# 16_-_HDMI.net
KiCad netlist of a schematic drawn in Altium Designer
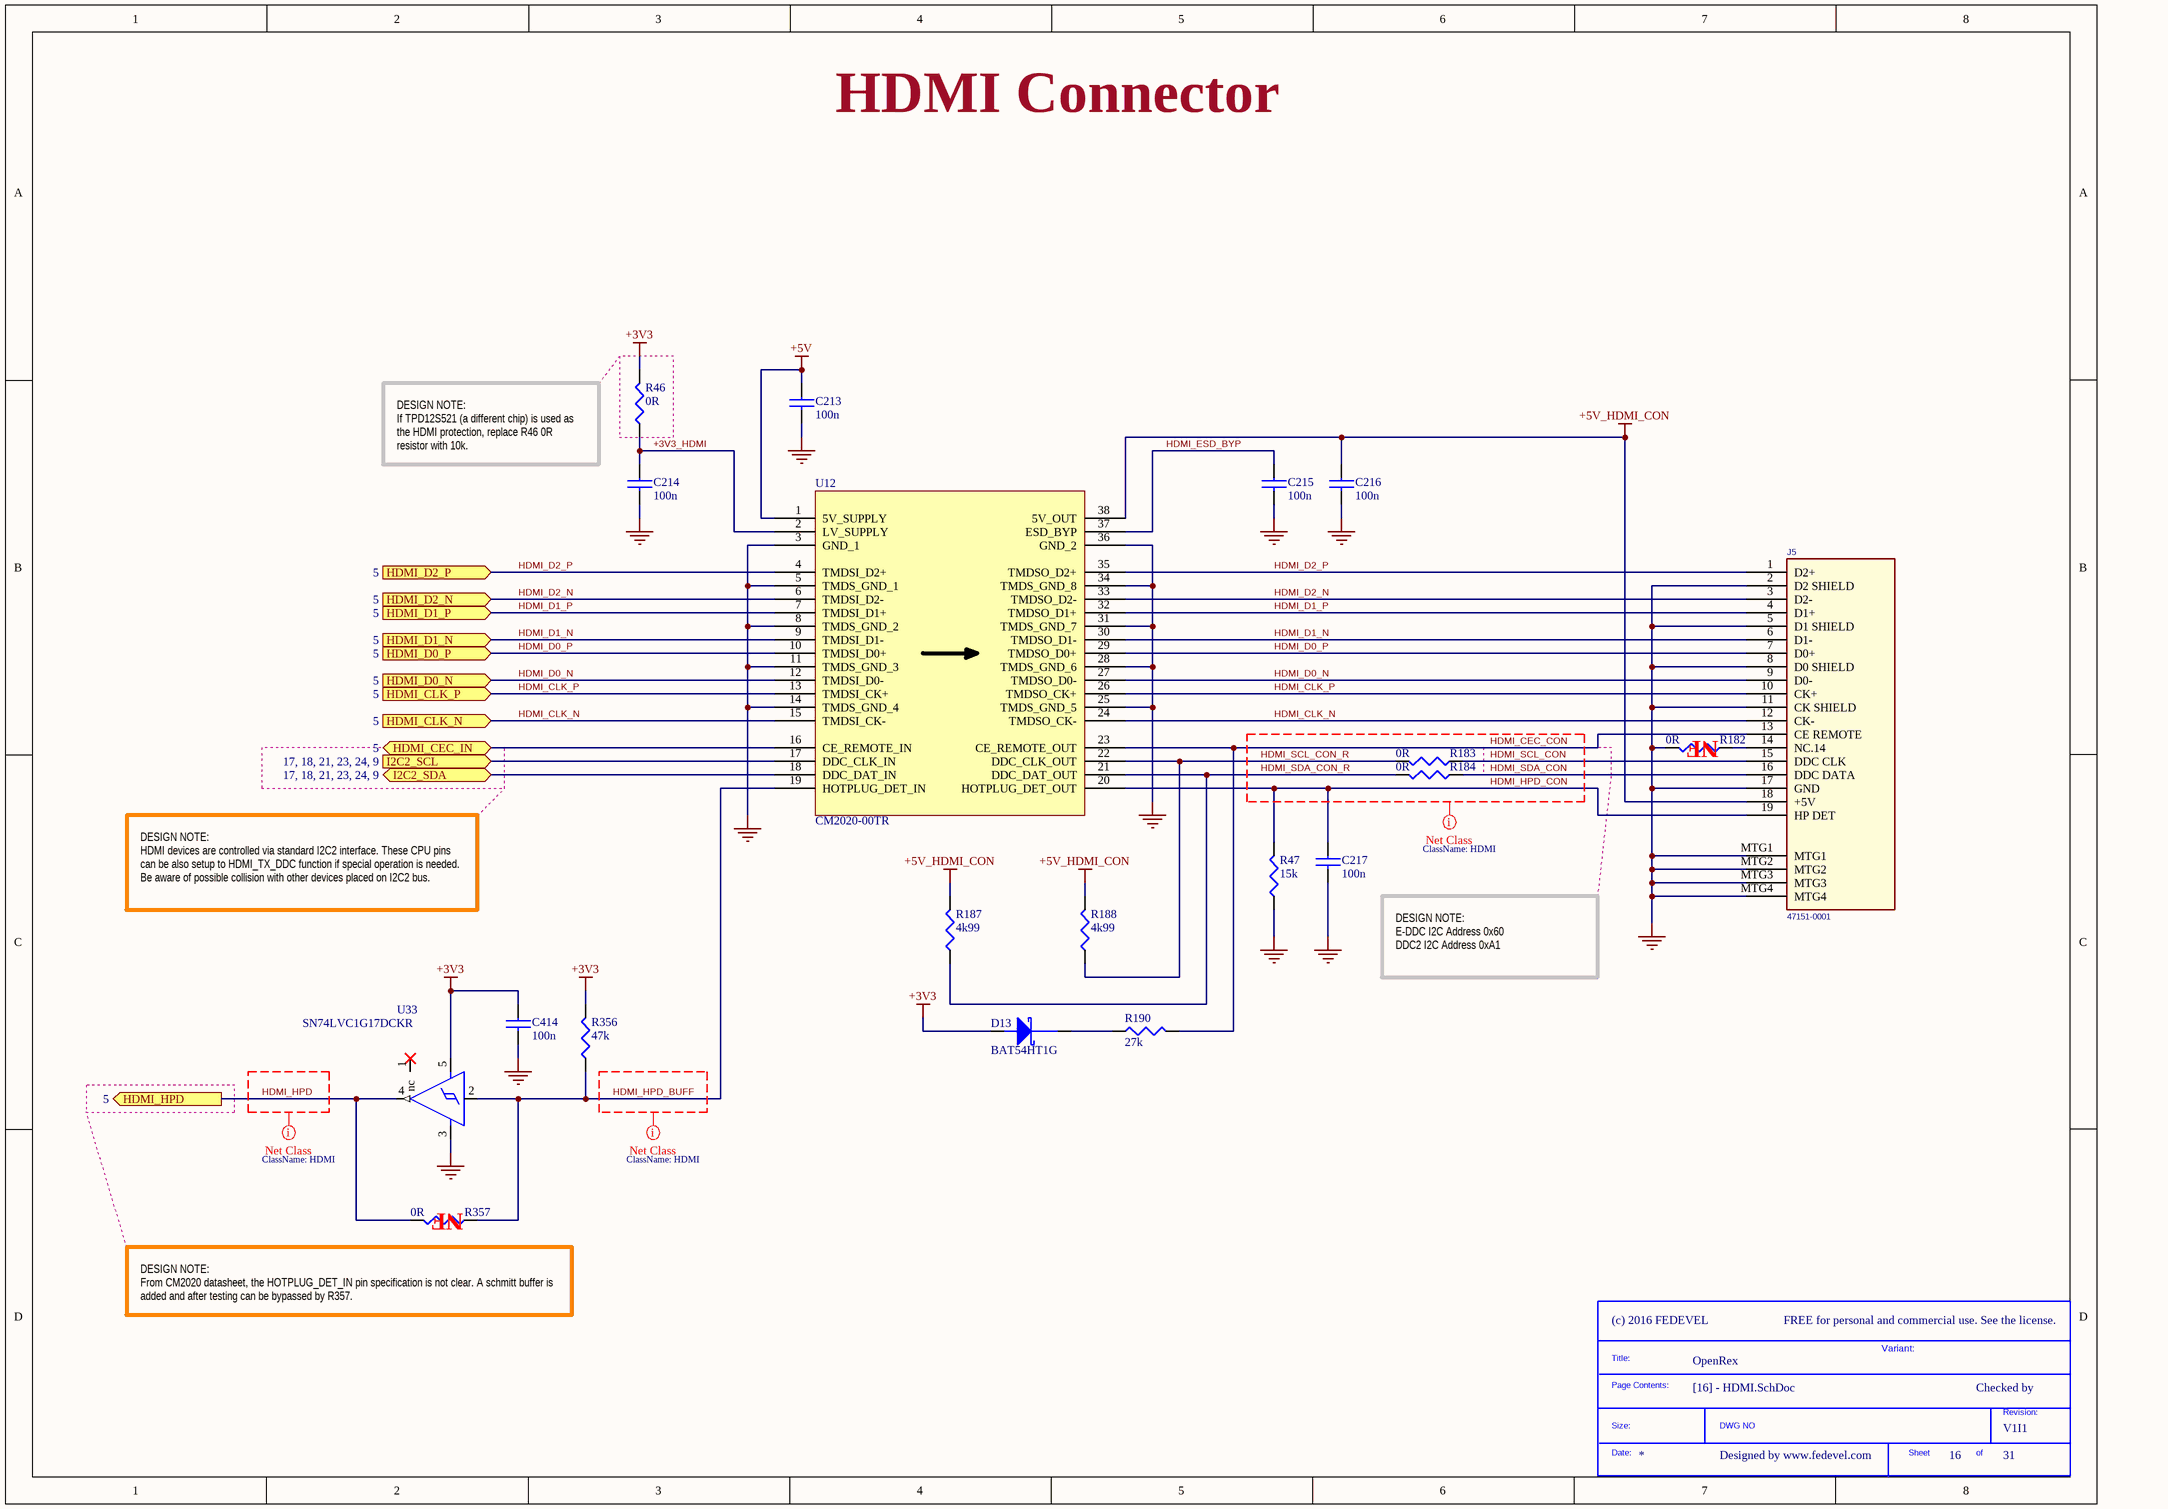
[diagram p0: [16] - HDMI.SchDoc]

(export (version "E")
  (design (tool "Eeschema 10.0.6"))
  (components
    (comp (ref "C213")
      (value "100n")
      (footprint "C0402")
      (description "CAP CER .10UF 50V X5R 10% 0402")
      (fields
        (field (name "MANUFACTURER") "TDK Corporation")
        (field (name "MANUFACTURER PART NUMBER") "C1005X5R1H104K")
      )
      (libsource (lib "Integrated_Library_FEDEVEL_APR_2015") (part "C1005X5R1H104K"))
    )
    (comp (ref "C214")
      (value "100n")
      (footprint "C0402")
      (description "CAP CER .10UF 50V X5R 10% 0402")
      (fields
        (field (name "MANUFACTURER") "TDK Corporation")
        (field (name "MANUFACTURER PART NUMBER") "C1005X5R1H104K")
      )
      (libsource (lib "Integrated_Library_FEDEVEL_APR_2015") (part "C1005X5R1H104K"))
    )
    (comp (ref "C215")
      (value "100n")
      (footprint "C0402")
      (description "CAP CER .10UF 50V X5R 10% 0402")
      (fields
        (field (name "MANUFACTURER") "TDK Corporation")
        (field (name "MANUFACTURER PART NUMBER") "C1005X5R1H104K")
      )
      (libsource (lib "Integrated_Library_FEDEVEL_APR_2015") (part "C1005X5R1H104K"))
    )
    (comp (ref "C216")
      (value "100n")
      (footprint "C0402")
      (description "CAP CER .10UF 50V X5R 10% 0402")
      (fields
        (field (name "MANUFACTURER") "TDK Corporation")
        (field (name "MANUFACTURER PART NUMBER") "C1005X5R1H104K")
      )
      (libsource (lib "Integrated_Library_FEDEVEL_APR_2015") (part "C1005X5R1H104K"))
    )
    (comp (ref "C217")
      (value "100n")
      (footprint "C0402")
      (description "CAP CER .10UF 50V X5R 10% 0402")
      (fields
        (field (name "MANUFACTURER") "TDK Corporation")
        (field (name "MANUFACTURER PART NUMBER") "C1005X5R1H104K")
      )
      (libsource (lib "Integrated_Library_FEDEVEL_APR_2015") (part "C1005X5R1H104K"))
    )
    (comp (ref "C414")
      (value "100n")
      (footprint "C0402")
      (description "CAP CER .10UF 50V X5R 10% 0402")
      (fields
        (field (name "MANUFACTURER") "TDK Corporation")
        (field (name "MANUFACTURER PART NUMBER") "C1005X5R1H104K")
      )
      (libsource (lib "Integrated_Library_FEDEVEL_APR_2015") (part "C1005X5R1H104K"))
    )
    (comp (ref "D13")
      (value "BAT54HT1G")
      (footprint "SOD323")
      (description "DIODE SCHOTTKY 30V 0.2A SOD323")
      (fields (field (name "MANUFACTURER") "Fairchild Semiconductor") (field (name ".CREATOR") "MM"))
      (libsource (lib "Integrated_Library_FEDEVEL_APR_2015") (part "BAT54HT1G"))
    )
    (comp (ref "J5")
      (value "47151-0001")
      (footprint "HDMI V1.1")
      (description "CONN RCPT 19POS HDMI RT ANG SMD")
      (fields
        (field (name "MANUFACTURER") "Molex Connector Corporation")
        (field (name ".CHECKED PCB") "MM")
        (field (name ".CHECKED SCH") "MM")
      )
      (libsource (lib "Integrated_Library_FEDEVEL_APR_2015") (part "47151-0001_v1.1"))
    )
    (comp (ref "R46")
      (value "0R")
      (footprint "R0402")
      (description "RES 0.0 OHM 1/16W 0402 SMD")
      (fields
        (field (name "MANUFACTURER") "Yageo")
        (field (name "MANUFACTURER PART NUMBER") "RC0402JR-070RL")
      )
      (libsource (lib "Integrated_Library_FEDEVEL_APR_2015") (part "RC0402JR-070RL"))
    )
    (comp (ref "R47")
      (value "15k")
      (footprint "R0402")
      (description "RES 15.0K OHM 1/16W 1% 0402 SMD")
      (fields
        (field (name "MANUFACTURER") "Yageo")
        (field (name "MANUFACTURER PART NUMBER") "RC0402FR-0715KL")
      )
      (libsource (lib "Integrated_Library_FEDEVEL_APR_2015") (part "RC0402FR-0715KL"))
    )
    (comp (ref "R182")
      (value "0R")
      (footprint "R0402")
      (description "RES 0.0 OHM 1/16W 0402 SMD")
      (fields
        (field (name "MANUFACTURER") "Yageo")
        (field (name "MANUFACTURER PART NUMBER") "RC0402JR-070RL")
      )
      (libsource (lib "Integrated_Library_FEDEVEL_APR_2015") (part "RC0402JR-070RL"))
    )
    (comp (ref "R183")
      (value "0R")
      (footprint "R0402")
      (description "RES 0.0 OHM 1/16W 0402 SMD")
      (fields
        (field (name "MANUFACTURER") "Yageo")
        (field (name "MANUFACTURER PART NUMBER") "RC0402JR-070RL")
      )
      (libsource (lib "Integrated_Library_FEDEVEL_APR_2015") (part "RC0402JR-070RL"))
    )
    (comp (ref "R184")
      (value "0R")
      (footprint "R0402")
      (description "RES 0.0 OHM 1/16W 0402 SMD")
      (fields
        (field (name "MANUFACTURER") "Yageo")
        (field (name "MANUFACTURER PART NUMBER") "RC0402JR-070RL")
      )
      (libsource (lib "Integrated_Library_FEDEVEL_APR_2015") (part "RC0402JR-070RL"))
    )
    (comp (ref "R187")
      (value "4k99")
      (footprint "R0402")
      (description "RES TF 4.99K OHM 1% 1/16W 0402")
      (fields
        (field (name "MANUFACTURER") "Stackpole Electronics Inc")
        (field (name "MANUFACTURER PART NUMBER") "RMCF0402FT4K99")
      )
      (libsource (lib "Integrated_Library_FEDEVEL_APR_2015") (part "RMCF0402FT4K99"))
    )
    (comp (ref "R188")
      (value "4k99")
      (footprint "R0402")
      (description "RES TF 4.99K OHM 1% 1/16W 0402")
      (fields
        (field (name "MANUFACTURER") "Stackpole Electronics Inc")
        (field (name "MANUFACTURER PART NUMBER") "RMCF0402FT4K99")
      )
      (libsource (lib "Integrated_Library_FEDEVEL_APR_2015") (part "RMCF0402FT4K99"))
    )
    (comp (ref "R190")
      (value "27k")
      (footprint "R0402")
      (description "RES 27.0K OHM 1/16W 1% 0402 SMD")
      (fields
        (field (name "MANUFACTURER") "Yageo")
        (field (name "MANUFACTURER PART NUMBER") "RC0402FR-0727KL")
      )
      (libsource (lib "Integrated_Library_FEDEVEL_APR_2015") (part "RC0402FR-0727KL"))
    )
    (comp (ref "R356")
      (value "47k")
      (footprint "R0402")
      (description "RES 47.0K OHM 1/16W 1% 0402 SMD")
      (fields
        (field (name "MANUFACTURER") "Yageo")
        (field (name "MANUFACTURER PART NUMBER") "RC0402FR-0747KL")
      )
      (libsource (lib "Integrated_Library_FEDEVEL_APR_2015") (part "RC0402FR-0747KL"))
    )
    (comp (ref "R357")
      (value "0R")
      (footprint "R0402")
      (description "RES 0.0 OHM 1/16W 0402 SMD")
      (fields
        (field (name "MANUFACTURER") "Yageo")
        (field (name "MANUFACTURER PART NUMBER") "RC0402JR-070RL")
      )
      (libsource (lib "Integrated_Library_FEDEVEL_APR_2015") (part "RC0402JR-070RL"))
    )
    (comp (ref "U12")
      (value "CM2020-00TR")
      (footprint "TSSOP_38")
      (description "IC HDMI TX PORT P/I 38-TSSOP")
      (fields (field (name "MANUFACTURER") "ON Semiconductor") (field (name ".CREATOR") "MM"))
      (libsource (lib "Integrated_Library_FEDEVEL_APR_2015") (part "CM2020-00TR"))
    )
    (comp (ref "U33")
      (value "SN74LVC1G17DCKR")
      (footprint "SC70_5")
      (description "IC BUFFER SCHMIT TRIG SC705")
      (fields
        (field (name "MANUFACTURER") "Texas Instruments")
        (field (name ".CHECKED PCB") "RF")
        (field (name ".CHECKED SCH") "RF")
      )
      (libsource (lib "Integrated_Library_FEDEVEL_APR_2015") (part "SN74LVC1G17DCKR"))
    )
  )
  (nets
    (net (code "1") (name "+3V3") (class "Default")
      (node (ref "C414") (pin "1") (pinfunction "1_1") (pintype "passive"))
      (node (ref "D13") (pin "2") (pinfunction "Anode_2") (pintype "passive"))
      (node (ref "R356") (pin "2") (pinfunction "2_2") (pintype "passive"))
      (node (ref "R46") (pin "2") (pinfunction "2_2") (pintype "passive"))
      (node (ref "U33") (pin "5") (pinfunction "NC1_5") (pintype "passive"))
    )
    (net (code "2") (name "+5V") (class "Default")
      (node (ref "C213") (pin "1") (pinfunction "1_1") (pintype "passive"))
      (node (ref "U12") (pin "1") (pinfunction "5V_SUPPLY_1") (pintype "passive"))
    )
    (net (code "3") (name "+5V_HDMI_CON") (class "Default")
      (node (ref "C216") (pin "1") (pinfunction "1_1") (pintype "passive"))
      (node (ref "J5") (pin "18") (pinfunction "+5V_18") (pintype "passive"))
      (node (ref "R187") (pin "2") (pinfunction "2_2") (pintype "passive"))
      (node (ref "R188") (pin "2") (pinfunction "2_2") (pintype "passive"))
      (node (ref "U12") (pin "38") (pinfunction "5V_OUT_38") (pintype "passive"))
    )
    (net (code "4") (name "/+3V3_HDMI") (class "Default")
      (node (ref "C214") (pin "1") (pinfunction "1_1") (pintype "passive"))
      (node (ref "R46") (pin "1") (pinfunction "1_1") (pintype "passive"))
      (node (ref "U12") (pin "2") (pinfunction "LV_SUPPLY_2") (pintype "passive"))
    )
    (net (code "5") (name "/HDMI_CEC_CON") (class "Default")
      (node (ref "J5") (pin "13") (pinfunction "CE_REMOTE_13") (pintype "passive"))
      (node (ref "R190") (pin "2") (pinfunction "2_2") (pintype "passive"))
      (node (ref "U12") (pin "23") (pinfunction "CE_REMOTE_OUT_23") (pintype "passive"))
    )
    (net (code "6") (name "/HDMI_CEC_IN") (class "Default")
      (node (ref "U12") (pin "16") (pinfunction "CE_REMOTE_IN_16") (pintype "passive"))
    )
    (net (code "7") (name "/HDMI_CLK_N") (class "Default")
      (node (ref "J5") (pin "12") (pinfunction "CK-_12") (pintype "passive"))
      (node (ref "U12") (pin "15") (pinfunction "TMDSI_CK-_15") (pintype "passive"))
      (node (ref "U12") (pin "24") (pinfunction "TMDSO_CK-_24") (pintype "passive"))
    )
    (net (code "8") (name "/HDMI_CLK_P") (class "Default")
      (node (ref "J5") (pin "10") (pinfunction "CK+_10") (pintype "passive"))
      (node (ref "U12") (pin "13") (pinfunction "TMDSI_CK+_13") (pintype "passive"))
      (node (ref "U12") (pin "26") (pinfunction "TMDSO_CK+_26") (pintype "passive"))
    )
    (net (code "9") (name "/HDMI_D0_N") (class "Default")
      (node (ref "J5") (pin "9") (pinfunction "D0-_9") (pintype "passive"))
      (node (ref "U12") (pin "12") (pinfunction "TMDSI_D0-_12") (pintype "passive"))
      (node (ref "U12") (pin "27") (pinfunction "TMDSO_D0-_27") (pintype "passive"))
    )
    (net (code "10") (name "/HDMI_D0_P") (class "Default")
      (node (ref "J5") (pin "7") (pinfunction "D0+_7") (pintype "passive"))
      (node (ref "U12") (pin "10") (pinfunction "TMDSI_D0+_10") (pintype "passive"))
      (node (ref "U12") (pin "29") (pinfunction "TMDSO_D0+_29") (pintype "passive"))
    )
    (net (code "11") (name "/HDMI_D1_N") (class "Default")
      (node (ref "J5") (pin "6") (pinfunction "D1-_6") (pintype "passive"))
      (node (ref "U12") (pin "30") (pinfunction "TMDSO_D1-_30") (pintype "passive"))
      (node (ref "U12") (pin "9") (pinfunction "TMDSI_D1-_9") (pintype "passive"))
    )
    (net (code "12") (name "/HDMI_D1_P") (class "Default")
      (node (ref "J5") (pin "4") (pinfunction "D1+_4") (pintype "passive"))
      (node (ref "U12") (pin "32") (pinfunction "TMDSO_D1+_32") (pintype "passive"))
      (node (ref "U12") (pin "7") (pinfunction "TMDSI_D1+_7") (pintype "passive"))
    )
    (net (code "13") (name "/HDMI_D2_N") (class "Default")
      (node (ref "J5") (pin "3") (pinfunction "D2-_3") (pintype "passive"))
      (node (ref "U12") (pin "33") (pinfunction "TMDSO_D2-_33") (pintype "passive"))
      (node (ref "U12") (pin "6") (pinfunction "TMDSI_D2-_6") (pintype "passive"))
    )
    (net (code "14") (name "/HDMI_D2_P") (class "Default")
      (node (ref "J5") (pin "1") (pinfunction "D2+_1") (pintype "passive"))
      (node (ref "U12") (pin "35") (pinfunction "TMDSO_D2+_35") (pintype "passive"))
      (node (ref "U12") (pin "4") (pinfunction "TMDSI_D2+_4") (pintype "passive"))
    )
    (net (code "15") (name "/HDMI_ESD_BYP") (class "Default")
      (node (ref "C215") (pin "1") (pinfunction "1_1") (pintype "passive"))
      (node (ref "U12") (pin "37") (pinfunction "ESD_BYP_37") (pintype "passive"))
    )
    (net (code "16") (name "/HDMI_HPD") (class "Default")
      (node (ref "R357") (pin "2") (pinfunction "2_2") (pintype "passive"))
      (node (ref "U33") (pin "4") (pinfunction "O_4") (pintype "output"))
    )
    (net (code "17") (name "/HDMI_HPD_BUFF") (class "Default")
      (node (ref "R356") (pin "1") (pinfunction "1_1") (pintype "passive"))
      (node (ref "R357") (pin "1") (pinfunction "1_1") (pintype "passive"))
      (node (ref "U12") (pin "19") (pinfunction "HOTPLUG_DET_IN_19") (pintype "passive"))
      (node (ref "U33") (pin "2") (pinfunction "I_2") (pintype "passive"))
    )
    (net (code "18") (name "/HDMI_HPD_CON") (class "Default")
      (node (ref "C217") (pin "1") (pinfunction "1_1") (pintype "passive"))
      (node (ref "J5") (pin "19") (pinfunction "HP_DET_19") (pintype "passive"))
      (node (ref "R47") (pin "2") (pinfunction "2_2") (pintype "passive"))
      (node (ref "U12") (pin "20") (pinfunction "HOTPLUG_DET_OUT_20") (pintype "passive"))
    )
    (net (code "19") (name "/HDMI_SCL_CON") (class "Default")
      (node (ref "J5") (pin "15") (pinfunction "DDC_CLK_15") (pintype "passive"))
      (node (ref "R183") (pin "1") (pinfunction "1_1") (pintype "passive"))
    )
    (net (code "20") (name "/HDMI_SCL_CON_R") (class "Default")
      (node (ref "R183") (pin "2") (pinfunction "2_2") (pintype "passive"))
      (node (ref "R188") (pin "1") (pinfunction "1_1") (pintype "passive"))
      (node (ref "U12") (pin "22") (pinfunction "DDC_CLK_OUT_22") (pintype "passive"))
    )
    (net (code "21") (name "/HDMI_SDA_CON") (class "Default")
      (node (ref "J5") (pin "16") (pinfunction "DDC_DATA_16") (pintype "passive"))
      (node (ref "R184") (pin "1") (pinfunction "1_1") (pintype "passive"))
    )
    (net (code "22") (name "/HDMI_SDA_CON_R") (class "Default")
      (node (ref "R184") (pin "2") (pinfunction "2_2") (pintype "passive"))
      (node (ref "R187") (pin "1") (pinfunction "1_1") (pintype "passive"))
      (node (ref "U12") (pin "21") (pinfunction "DDC_DAT_OUT_21") (pintype "passive"))
    )
    (net (code "23") (name "/I2C2_SCL") (class "Default")
      (node (ref "U12") (pin "17") (pinfunction "DDC_CLK_IN_17") (pintype "passive"))
    )
    (net (code "24") (name "/I2C2_SDA") (class "Default")
      (node (ref "U12") (pin "18") (pinfunction "DDC_DAT_IN_18") (pintype "passive"))
    )
    (net (code "25") (name "GND") (class "Default")
      (node (ref "C213") (pin "2") (pinfunction "2_2") (pintype "passive"))
      (node (ref "C214") (pin "2") (pinfunction "2_2") (pintype "passive"))
      (node (ref "C215") (pin "2") (pinfunction "2_2") (pintype "passive"))
      (node (ref "C216") (pin "2") (pinfunction "2_2") (pintype "passive"))
      (node (ref "C217") (pin "2") (pinfunction "2_2") (pintype "passive"))
      (node (ref "C414") (pin "2") (pinfunction "2_2") (pintype "passive"))
      (node (ref "J5") (pin "11") (pinfunction "CK_SHIELD_11") (pintype "passive"))
      (node (ref "J5") (pin "17") (pinfunction "GND_17") (pintype "passive"))
      (node (ref "J5") (pin "2") (pinfunction "D2_SHIELD_2") (pintype "passive"))
      (node (ref "J5") (pin "5") (pinfunction "D1_SHIELD_5") (pintype "passive"))
      (node (ref "J5") (pin "8") (pinfunction "D0_SHIELD_8") (pintype "passive"))
      (node (ref "J5") (pin "MTG1") (pinfunction "MTG1_MTG1") (pintype "passive"))
      (node (ref "J5") (pin "MTG2") (pinfunction "MTG2_MTG2") (pintype "passive"))
      (node (ref "J5") (pin "MTG3") (pinfunction "MTG3_MTG3") (pintype "passive"))
      (node (ref "J5") (pin "MTG4") (pinfunction "MTG4_MTG4") (pintype "passive"))
      (node (ref "R182") (pin "2") (pinfunction "2_2") (pintype "passive"))
      (node (ref "R47") (pin "1") (pinfunction "1_1") (pintype "passive"))
      (node (ref "U12") (pin "11") (pinfunction "TMDS_GND_3_11") (pintype "passive"))
      (node (ref "U12") (pin "14") (pinfunction "TMDS_GND_4_14") (pintype "passive"))
      (node (ref "U12") (pin "25") (pinfunction "TMDS_GND_5_25") (pintype "passive"))
      (node (ref "U12") (pin "28") (pinfunction "TMDS_GND_6_28") (pintype "passive"))
      (node (ref "U12") (pin "3") (pinfunction "GND_1_3") (pintype "passive"))
      (node (ref "U12") (pin "31") (pinfunction "TMDS_GND_7_31") (pintype "passive"))
      (node (ref "U12") (pin "34") (pinfunction "TMDS_GND_8_34") (pintype "passive"))
      (node (ref "U12") (pin "36") (pinfunction "GND_2_36") (pintype "passive"))
      (node (ref "U12") (pin "5") (pinfunction "TMDS_GND_1_5") (pintype "passive"))
      (node (ref "U12") (pin "8") (pinfunction "TMDS_GND_2_8") (pintype "passive"))
      (node (ref "U33") (pin "3") (pinfunction "GND_3") (pintype "passive"))
    )
    (net (code "26") (name "Net-(D13-Cathode)") (class "Default")
      (node (ref "D13") (pin "1") (pinfunction "Cathode_1") (pintype "passive"))
      (node (ref "R190") (pin "1") (pinfunction "1_1") (pintype "passive"))
    )
    (net (code "27") (name "Net-(J5-NC.14)") (class "Default")
      (node (ref "J5") (pin "14") (pinfunction "NC.14_14") (pintype "passive"))
      (node (ref "R182") (pin "1") (pinfunction "1_1") (pintype "passive"))
    )
    (net (code "28") (name "unconnected-(U33-nc-Pad1)") (class "Default")
      (node (ref "U33") (pin "1") (pinfunction "nc_1") (pintype "passive+no_connect"))
    )
  )
)
